# payloaduplink.net
KiCad netlist of a schematic drawn in EAGLE
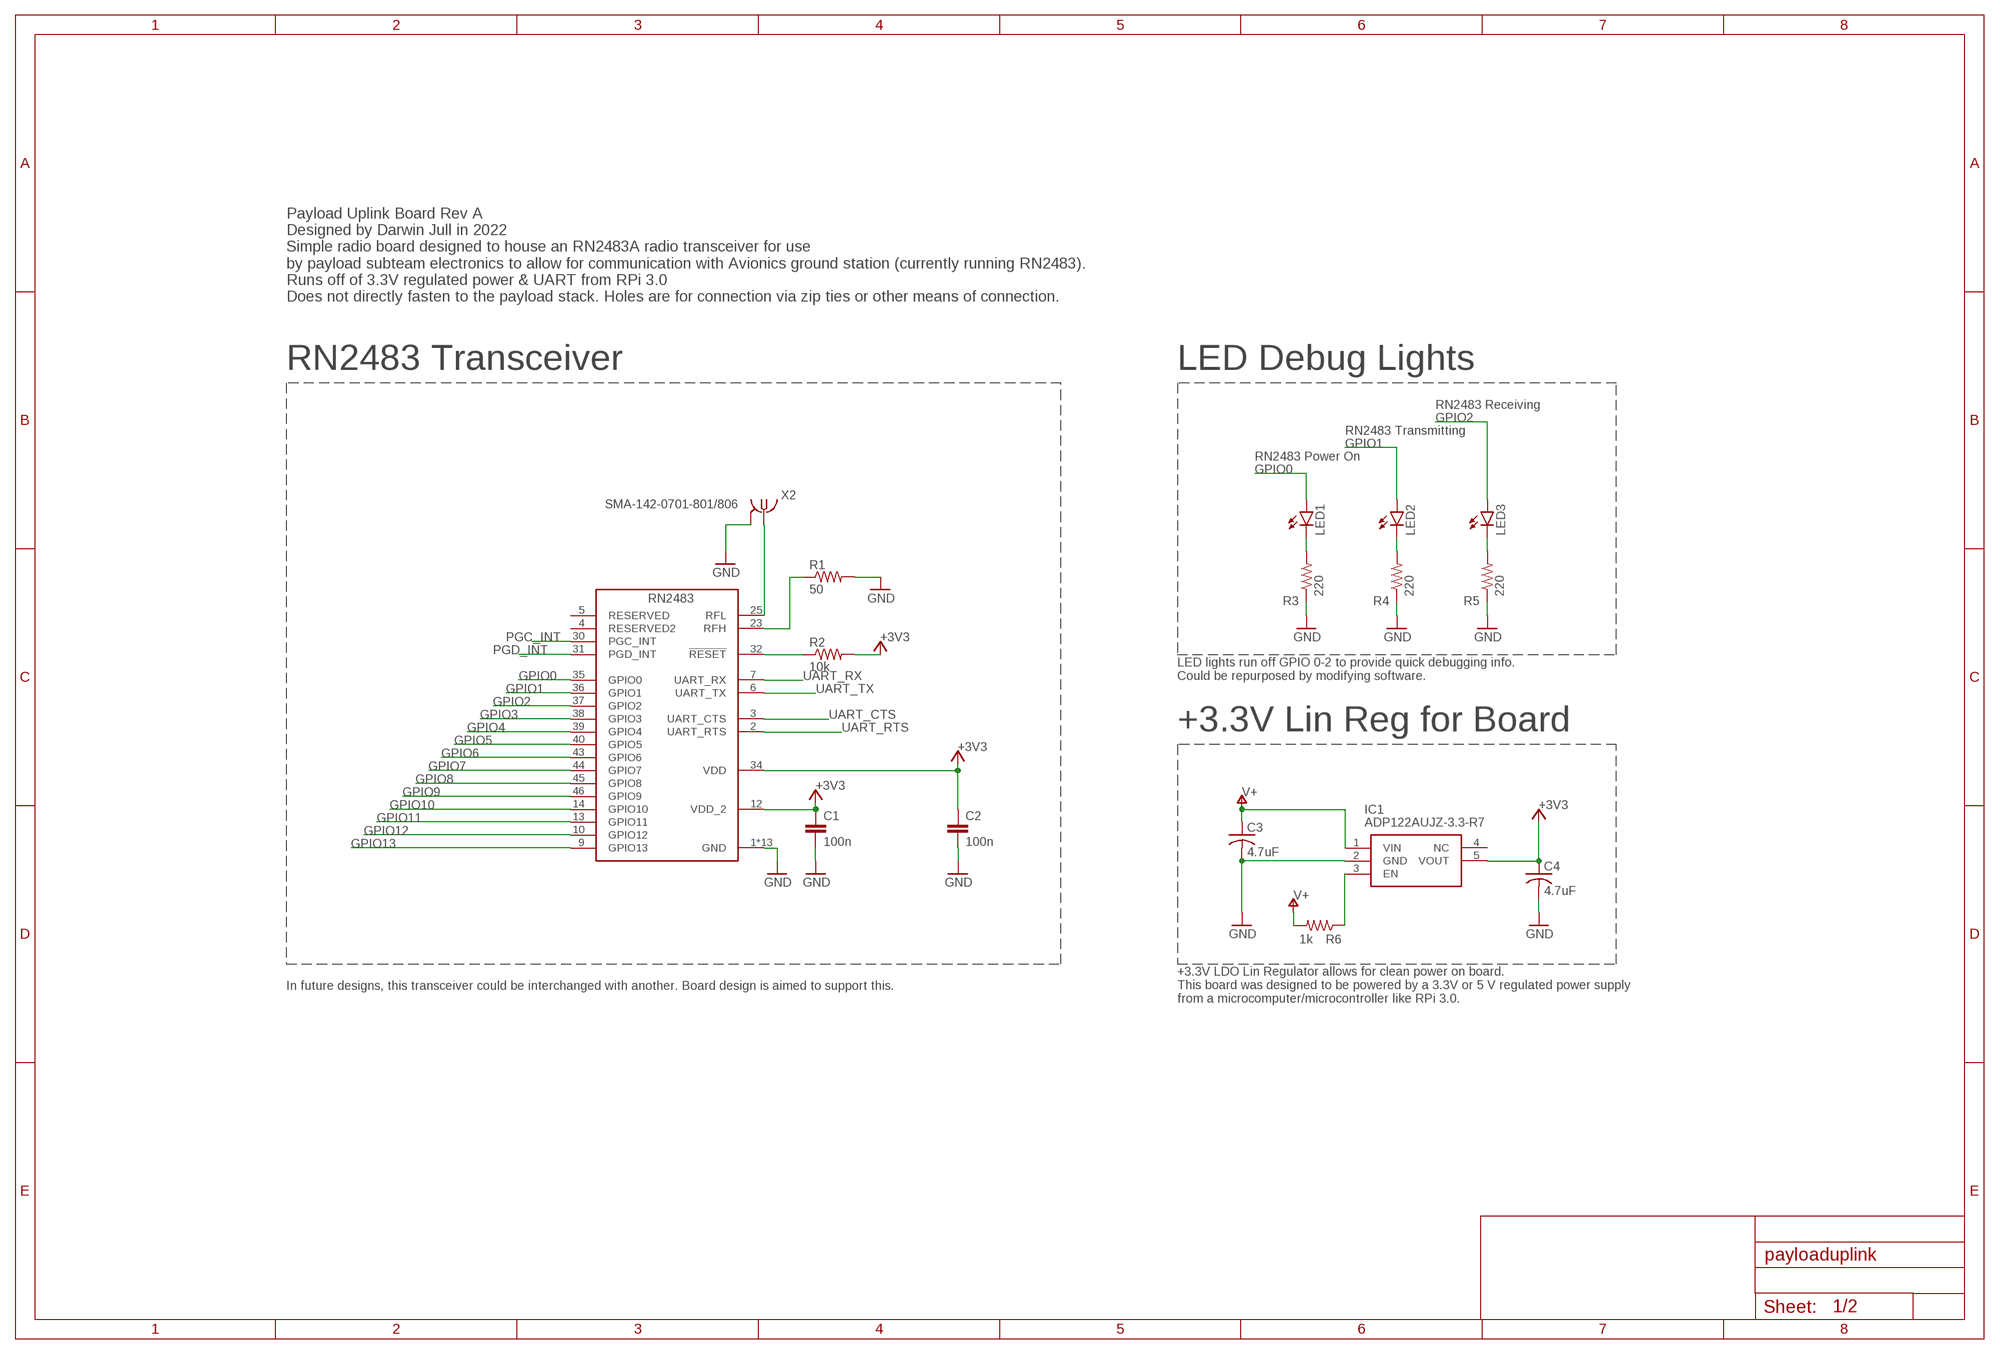
[diagram p0: schematic, sheet 1]
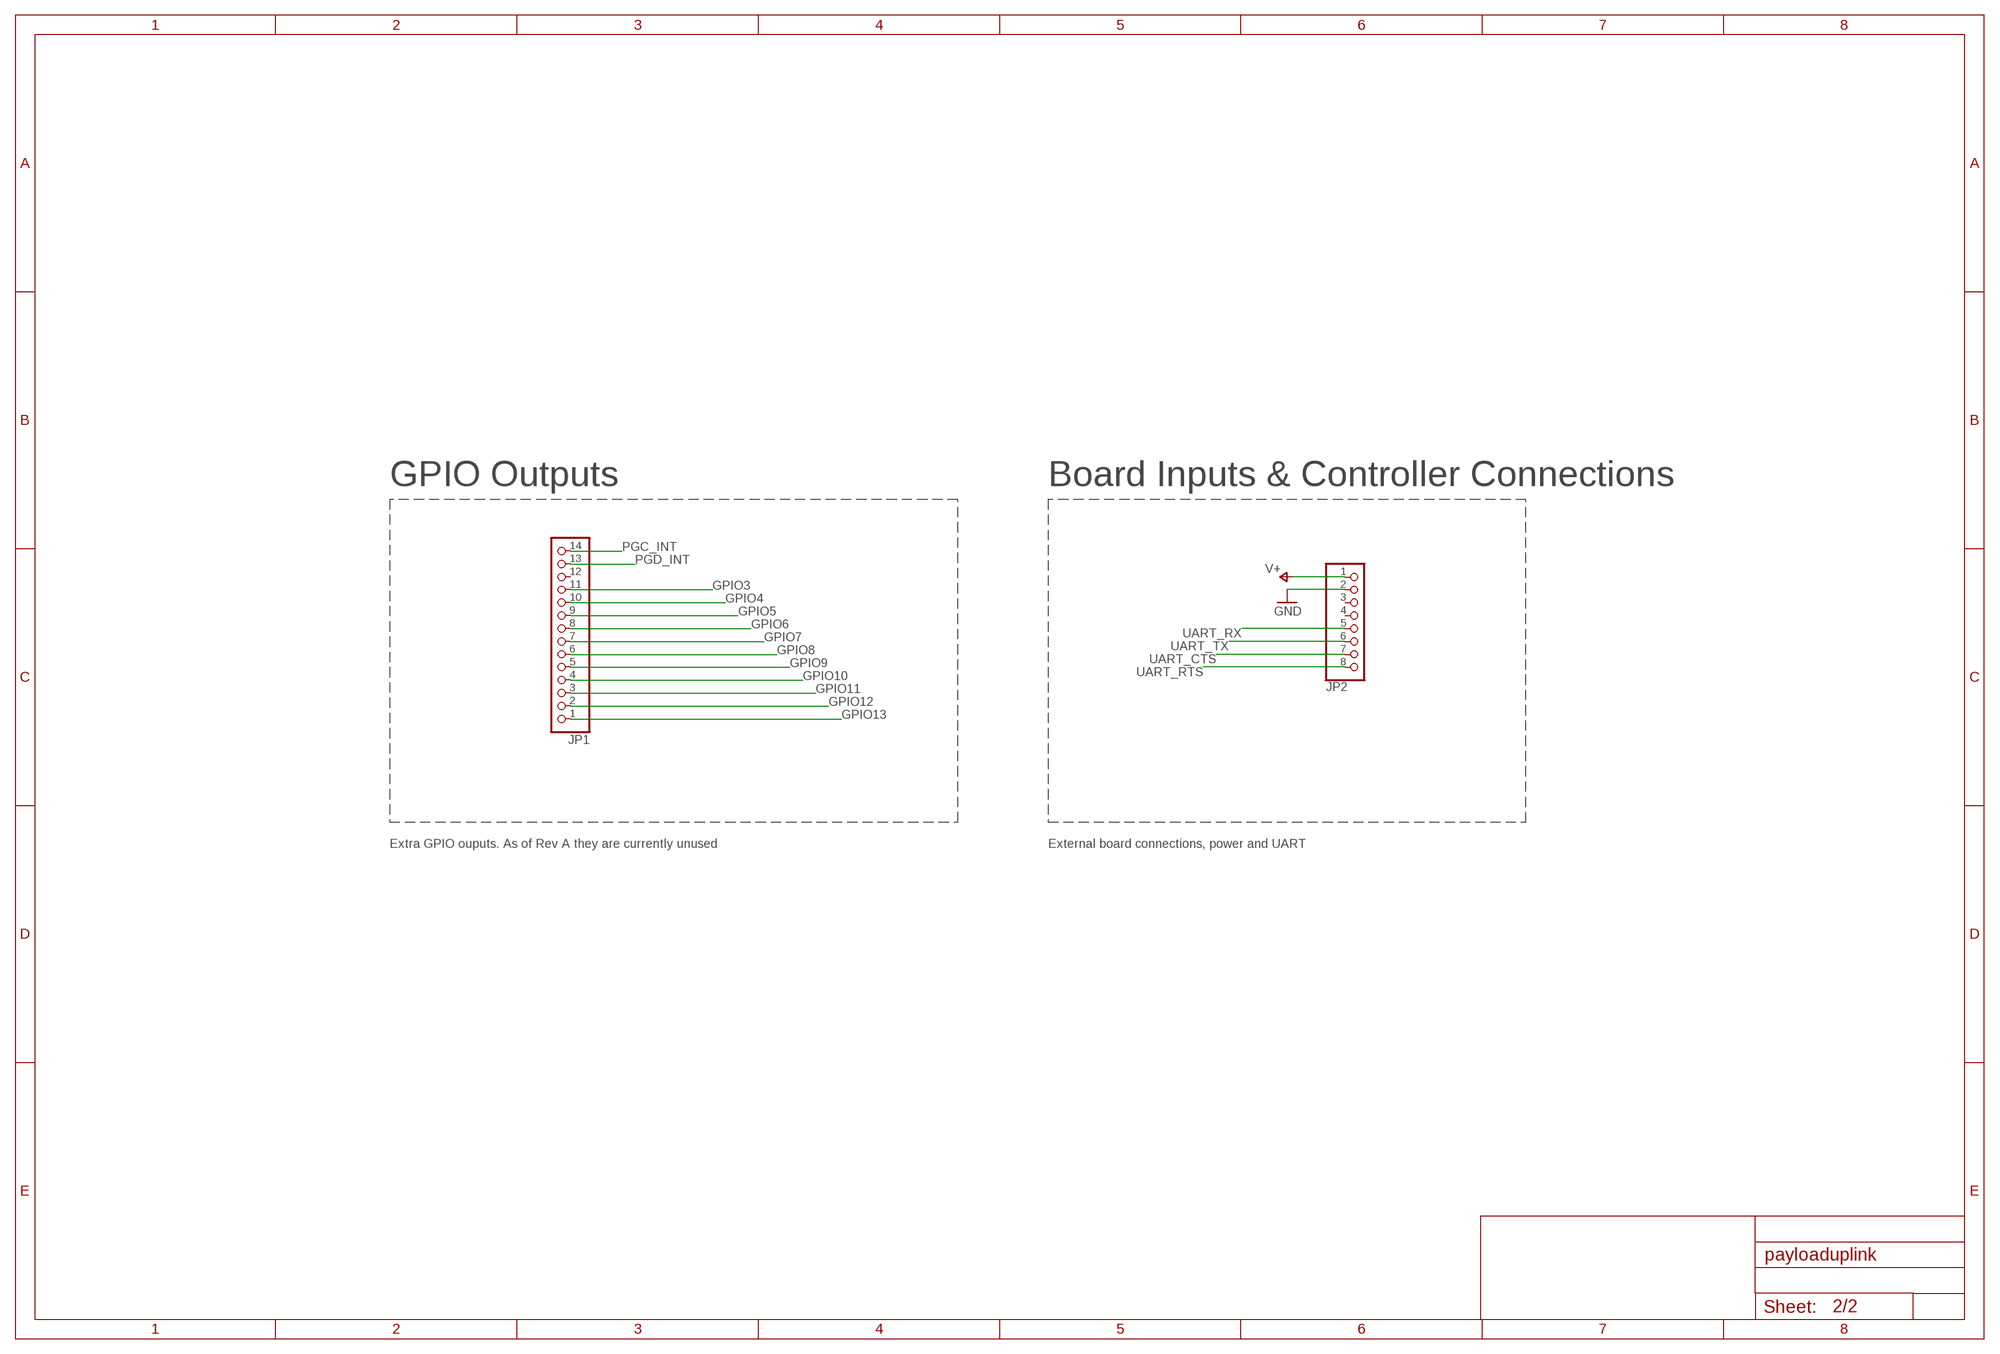
[diagram p1: schematic, sheet 2]

(export (version "E")
  (design (tool "Eeschema 10.0.6"))
  (components
    (comp (ref "C1")
      (value "100n")
      (footprint "eagle-import:C0805")
      (libsource (lib "eagle-import") (part "C-EUC0805"))
    )
    (comp (ref "C2")
      (value "100n")
      (footprint "eagle-import:C0805")
      (libsource (lib "eagle-import") (part "C-EUC0805"))
    )
    (comp (ref "C3")
      (value "4.7uF")
      (footprint "eagle-import:C0805")
      (libsource (lib "eagle-import") (part "C-USC0805"))
    )
    (comp (ref "C4")
      (value "4.7uF")
      (footprint "eagle-import:C0805")
      (libsource (lib "eagle-import") (part "C-USC0805"))
    )
    (comp (ref "IC1")
      (value "ADP122AUJZ-3.3-R7")
      (footprint "eagle-import:SOT95P280X100-5N")
      (fields (field (name "MOUSER_PART_NUMBER") "584-ADP122AUJZ-3.3R7"))
      (libsource (lib "eagle-import") (part "ADP122AUJZ-3.3-R7"))
    )
    (comp (ref "LED1")
      (value "LEDCHIPLED_0603")
      (footprint "eagle-import:CHIPLED_0603")
      (libsource (lib "eagle-import") (part "LEDCHIPLED_0603"))
    )
    (comp (ref "LED2")
      (value "LEDCHIPLED_0603")
      (footprint "eagle-import:CHIPLED_0603")
      (libsource (lib "eagle-import") (part "LEDCHIPLED_0603"))
    )
    (comp (ref "LED3")
      (value "LEDCHIPLED_0603")
      (footprint "eagle-import:CHIPLED_0603")
      (libsource (lib "eagle-import") (part "LEDCHIPLED_0603"))
    )
    (comp (ref "R1")
      (value "50")
      (footprint "eagle-import:R0402")
      (libsource (lib "eagle-import") (part "R-US_R0402"))
    )
    (comp (ref "R2")
      (value "10k")
      (footprint "eagle-import:R0805")
      (libsource (lib "eagle-import") (part "R-US_R0805"))
    )
    (comp (ref "R3")
      (value "220")
      (footprint "eagle-import:R0805")
      (libsource (lib "eagle-import") (part "R-US_R0805"))
    )
    (comp (ref "R4")
      (value "220")
      (footprint "eagle-import:R0805")
      (libsource (lib "eagle-import") (part "R-US_R0805"))
    )
    (comp (ref "R5")
      (value "220")
      (footprint "eagle-import:R0805")
      (libsource (lib "eagle-import") (part "R-US_R0805"))
    )
    (comp (ref "R6")
      (value "1k")
      (footprint "eagle-import:R0805")
      (libsource (lib "eagle-import") (part "R-US_R0805"))
    )
    (comp (ref "U$1")
      (value "RN2483_TRANSCIEVER")
      (footprint "eagle-import:RN2483")
      (libsource (lib "eagle-import") (part "RN2483_TRANSCIEVER"))
    )
    (comp (ref "X2")
      (value "SMA-142-0701-801/806")
      (footprint "eagle-import:J502-ND-142-0701-801_806")
      (fields (field (name "MF") "JOHNSON COMPONENTS") (field (name "MPN") "142-0701-801"))
      (libsource (lib "eagle-import") (part "SMA-142-0701-801/806"))
    )
    (comp (ref "JP1")
      (value "PINHD-1X14")
      (footprint "eagle-import:1X14")
      (libsource (lib "eagle-import") (part "PINHD-1X14"))
    )
    (comp (ref "JP2")
      (value "PINHD-1X8")
      (footprint "eagle-import:1X08")
      (libsource (lib "eagle-import") (part "PINHD-1X8"))
    )
  )
  (nets
    (net (code "1") (name "+3V3") (class "Default")
      (node (ref "C1") (pin "1") (pinfunction "1_1") (pintype "passive"))
      (node (ref "C2") (pin "1") (pinfunction "1_1") (pintype "passive"))
      (node (ref "C4") (pin "1") (pinfunction "1_1") (pintype "passive"))
      (node (ref "IC1") (pin "5") (pinfunction "VOUT_5") (pintype "bidirectional"))
      (node (ref "R2") (pin "2") (pinfunction "2_2") (pintype "passive"))
      (node (ref "U$1") (pin "12") (pinfunction "VDD_2_12") (pintype "bidirectional"))
      (node (ref "U$1") (pin "34") (pinfunction "VDD_34") (pintype "bidirectional"))
    )
    (net (code "2") (name "GND") (class "Default")
      (node (ref "C1") (pin "2") (pinfunction "2_2") (pintype "passive"))
      (node (ref "C2") (pin "2") (pinfunction "2_2") (pintype "passive"))
      (node (ref "C3") (pin "2") (pinfunction "2_2") (pintype "passive"))
      (node (ref "C4") (pin "2") (pinfunction "2_2") (pintype "passive"))
      (node (ref "IC1") (pin "2") (pinfunction "GND_2") (pintype "bidirectional"))
      (node (ref "JP2") (pin "2") (pinfunction "2_2") (pintype "passive"))
      (node (ref "R1") (pin "2") (pinfunction "2_2") (pintype "passive"))
      (node (ref "R3") (pin "1") (pinfunction "1_1") (pintype "passive"))
      (node (ref "R4") (pin "1") (pinfunction "1_1") (pintype "passive"))
      (node (ref "R5") (pin "1") (pinfunction "1_1") (pintype "passive"))
      (node (ref "U$1") (pin "1") (pinfunction "GND_1") (pintype "bidirectional"))
      (node (ref "U$1") (pin "11") (pinfunction "GND_11") (pintype "bidirectional"))
      (node (ref "U$1") (pin "20") (pinfunction "GND_20") (pintype "bidirectional"))
      (node (ref "U$1") (pin "21") (pinfunction "GND_21") (pintype "bidirectional"))
      (node (ref "U$1") (pin "22") (pinfunction "GND_22") (pintype "bidirectional"))
      (node (ref "U$1") (pin "24") (pinfunction "GND_24") (pintype "bidirectional"))
      (node (ref "U$1") (pin "26") (pinfunction "GND_26") (pintype "bidirectional"))
      (node (ref "U$1") (pin "27") (pinfunction "GND_27") (pintype "bidirectional"))
      (node (ref "U$1") (pin "28") (pinfunction "GND_28") (pintype "bidirectional"))
      (node (ref "U$1") (pin "33") (pinfunction "GND_33") (pintype "bidirectional"))
      (node (ref "U$1") (pin "41") (pinfunction "GND_41") (pintype "bidirectional"))
      (node (ref "U$1") (pin "47") (pinfunction "GND_47") (pintype "bidirectional"))
      (node (ref "U$1") (pin "8") (pinfunction "GND_8") (pintype "bidirectional"))
      (node (ref "X2") (pin "G@1") (pinfunction "2_G@1") (pintype "passive"))
      (node (ref "X2") (pin "G@2") (pinfunction "2_G@2") (pintype "passive"))
      (node (ref "X2") (pin "G@3") (pinfunction "2_G@3") (pintype "passive"))
      (node (ref "X2") (pin "G@4") (pinfunction "2_G@4") (pintype "passive"))
    )
    (net (code "3") (name "GPIO0") (class "Default")
      (node (ref "LED1") (pin "A") (pinfunction "A_A") (pintype "passive"))
      (node (ref "U$1") (pin "35") (pinfunction "GPIO0_35") (pintype "bidirectional"))
    )
    (net (code "4") (name "GPIO1") (class "Default")
      (node (ref "LED2") (pin "A") (pinfunction "A_A") (pintype "passive"))
      (node (ref "U$1") (pin "36") (pinfunction "GPIO1_36") (pintype "bidirectional"))
    )
    (net (code "5") (name "GPIO2") (class "Default")
      (node (ref "LED3") (pin "A") (pinfunction "A_A") (pintype "passive"))
      (node (ref "U$1") (pin "37") (pinfunction "GPIO2_37") (pintype "bidirectional"))
    )
    (net (code "6") (name "GPIO3") (class "Default")
      (node (ref "JP1") (pin "11") (pinfunction "11_11") (pintype "passive"))
      (node (ref "U$1") (pin "38") (pinfunction "GPIO3_38") (pintype "bidirectional"))
    )
    (net (code "7") (name "GPIO4") (class "Default")
      (node (ref "JP1") (pin "10") (pinfunction "10_10") (pintype "passive"))
      (node (ref "U$1") (pin "39") (pinfunction "GPIO4_39") (pintype "bidirectional"))
    )
    (net (code "8") (name "GPIO5") (class "Default")
      (node (ref "JP1") (pin "9") (pinfunction "9_9") (pintype "passive"))
      (node (ref "U$1") (pin "40") (pinfunction "GPIO5_40") (pintype "bidirectional"))
    )
    (net (code "9") (name "GPIO6") (class "Default")
      (node (ref "JP1") (pin "8") (pinfunction "8_8") (pintype "passive"))
      (node (ref "U$1") (pin "43") (pinfunction "GPIO6_43") (pintype "bidirectional"))
    )
    (net (code "10") (name "GPIO7") (class "Default")
      (node (ref "JP1") (pin "7") (pinfunction "7_7") (pintype "passive"))
      (node (ref "U$1") (pin "44") (pinfunction "GPIO7_44") (pintype "bidirectional"))
    )
    (net (code "11") (name "GPIO8") (class "Default")
      (node (ref "JP1") (pin "6") (pinfunction "6_6") (pintype "passive"))
      (node (ref "U$1") (pin "45") (pinfunction "GPIO8_45") (pintype "bidirectional"))
    )
    (net (code "12") (name "GPIO9") (class "Default")
      (node (ref "JP1") (pin "5") (pinfunction "5_5") (pintype "passive"))
      (node (ref "U$1") (pin "46") (pinfunction "GPIO9_46") (pintype "bidirectional"))
    )
    (net (code "13") (name "GPIO10") (class "Default")
      (node (ref "JP1") (pin "4") (pinfunction "4_4") (pintype "passive"))
      (node (ref "U$1") (pin "14") (pinfunction "GPIO10_14") (pintype "bidirectional"))
    )
    (net (code "14") (name "GPIO11") (class "Default")
      (node (ref "JP1") (pin "3") (pinfunction "3_3") (pintype "passive"))
      (node (ref "U$1") (pin "13") (pinfunction "GPIO11_13") (pintype "bidirectional"))
    )
    (net (code "15") (name "GPIO12") (class "Default")
      (node (ref "JP1") (pin "2") (pinfunction "2_2") (pintype "passive"))
      (node (ref "U$1") (pin "10") (pinfunction "GPIO12_10") (pintype "bidirectional"))
    )
    (net (code "16") (name "GPIO13") (class "Default")
      (node (ref "JP1") (pin "1") (pinfunction "1_1") (pintype "passive"))
      (node (ref "U$1") (pin "9") (pinfunction "GPIO13_9") (pintype "bidirectional"))
    )
    (net (code "17") (name "Net-(IC1-EN)") (class "Default")
      (node (ref "IC1") (pin "3") (pinfunction "EN_3") (pintype "bidirectional"))
      (node (ref "R6") (pin "1") (pinfunction "1_1") (pintype "passive"))
    )
    (net (code "18") (name "Net-(LED1-PadC)") (class "Default")
      (node (ref "LED1") (pin "C") (pinfunction "C_C") (pintype "passive"))
      (node (ref "R3") (pin "2") (pinfunction "2_2") (pintype "passive"))
    )
    (net (code "19") (name "Net-(LED2-PadC)") (class "Default")
      (node (ref "LED2") (pin "C") (pinfunction "C_C") (pintype "passive"))
      (node (ref "R4") (pin "2") (pinfunction "2_2") (pintype "passive"))
    )
    (net (code "20") (name "Net-(LED3-PadC)") (class "Default")
      (node (ref "LED3") (pin "C") (pinfunction "C_C") (pintype "passive"))
      (node (ref "R5") (pin "2") (pinfunction "2_2") (pintype "passive"))
    )
    (net (code "21") (name "Net-(U$1-RFH)") (class "Default")
      (node (ref "R1") (pin "1") (pinfunction "1_1") (pintype "passive"))
      (node (ref "U$1") (pin "23") (pinfunction "RFH_23") (pintype "bidirectional"))
    )
    (net (code "22") (name "Net-(U$1-RFL)") (class "Default")
      (node (ref "U$1") (pin "25") (pinfunction "RFL_25") (pintype "bidirectional"))
      (node (ref "X2") (pin "1") (pinfunction "1_1") (pintype "passive"))
    )
    (net (code "23") (name "Net-(U$1-~{RESET})") (class "Default")
      (node (ref "R2") (pin "1") (pinfunction "1_1") (pintype "passive"))
      (node (ref "U$1") (pin "32") (pinfunction "~{RESET}_32") (pintype "bidirectional"))
    )
    (net (code "24") (name "PGC_INT") (class "Default")
      (node (ref "JP1") (pin "14") (pinfunction "14_14") (pintype "passive"))
      (node (ref "U$1") (pin "30") (pinfunction "PGC_INT_30") (pintype "bidirectional"))
    )
    (net (code "25") (name "PGD_INT") (class "Default")
      (node (ref "JP1") (pin "13") (pinfunction "13_13") (pintype "passive"))
      (node (ref "U$1") (pin "31") (pinfunction "PGD_INT_31") (pintype "bidirectional"))
    )
    (net (code "26") (name "UART_CTS") (class "Default")
      (node (ref "JP2") (pin "7") (pinfunction "7_7") (pintype "passive"))
      (node (ref "U$1") (pin "3") (pinfunction "UART_CTS_3") (pintype "bidirectional"))
    )
    (net (code "27") (name "UART_RTS") (class "Default")
      (node (ref "JP2") (pin "8") (pinfunction "8_8") (pintype "passive"))
      (node (ref "U$1") (pin "2") (pinfunction "UART_RTS_2") (pintype "bidirectional"))
    )
    (net (code "28") (name "UART_RX") (class "Default")
      (node (ref "JP2") (pin "5") (pinfunction "5_5") (pintype "passive"))
      (node (ref "U$1") (pin "7") (pinfunction "UART_RX_7") (pintype "bidirectional"))
    )
    (net (code "29") (name "UART_TX") (class "Default")
      (node (ref "JP2") (pin "6") (pinfunction "6_6") (pintype "passive"))
      (node (ref "U$1") (pin "6") (pinfunction "UART_TX_6") (pintype "bidirectional"))
    )
    (net (code "30") (name "V+") (class "Default")
      (node (ref "C3") (pin "1") (pinfunction "1_1") (pintype "passive"))
      (node (ref "IC1") (pin "1") (pinfunction "VIN_1") (pintype "bidirectional"))
      (node (ref "JP2") (pin "1") (pinfunction "1_1") (pintype "passive"))
      (node (ref "R6") (pin "2") (pinfunction "2_2") (pintype "passive"))
    )
    (net (code "31") (name "unconnected-(IC1-NC-Pad4)") (class "Default")
      (node (ref "IC1") (pin "4") (pinfunction "NC_4") (pintype "no_connect"))
    )
    (net (code "32") (name "unconnected-(JP1-Pad12)") (class "Default")
      (node (ref "JP1") (pin "12") (pinfunction "12_12") (pintype "passive"))
    )
    (net (code "33") (name "unconnected-(JP2-Pad3)") (class "Default")
      (node (ref "JP2") (pin "3") (pinfunction "3_3") (pintype "passive"))
    )
    (net (code "34") (name "unconnected-(JP2-Pad4)") (class "Default")
      (node (ref "JP2") (pin "4") (pinfunction "4_4") (pintype "passive"))
    )
    (net (code "35") (name "unconnected-(U$1-RESERVED-Pad5)") (class "Default")
      (node (ref "U$1") (pin "5") (pinfunction "RESERVED_5") (pintype "bidirectional"))
    )
    (net (code "36") (name "unconnected-(U$1-RESERVED2-Pad4)") (class "Default")
      (node (ref "U$1") (pin "4") (pinfunction "RESERVED2_4") (pintype "bidirectional"))
    )
  )
)
